# user_interface.net
KiCad netlist of a schematic drawn in Altium Designer
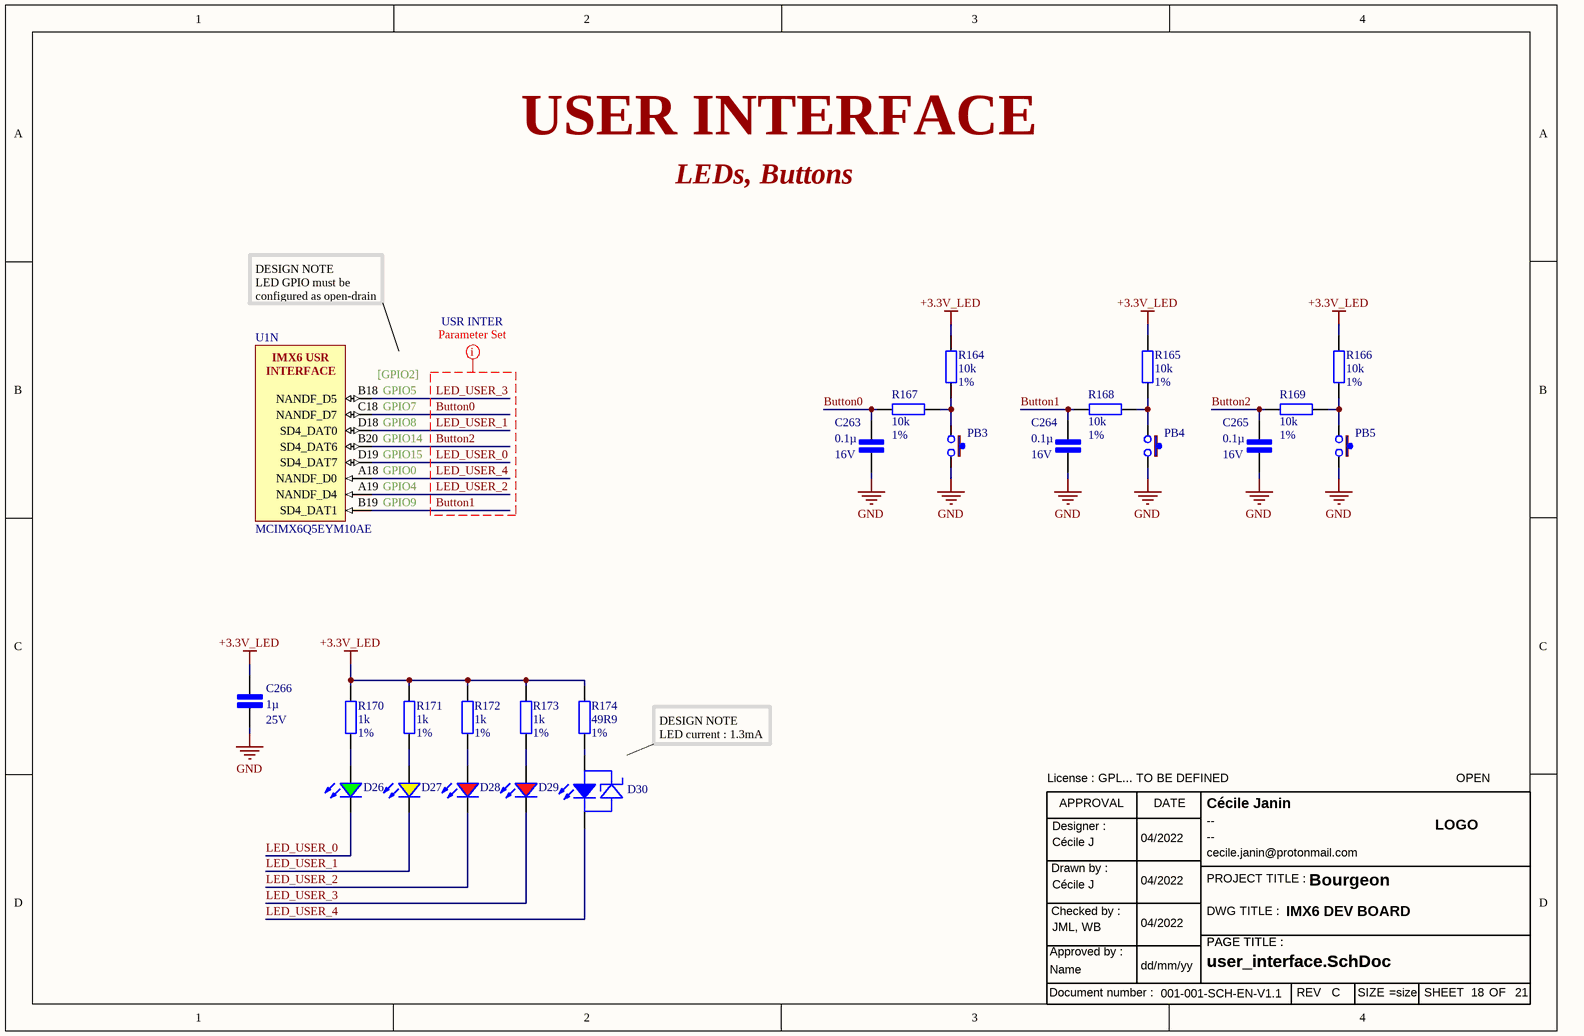
[diagram p0: user_interface.SchDoc]

(export (version "E")
  (design (tool "Eeschema 10.0.6"))
  (components
    (comp (ref "C263")
      (value "0.1µ")
      (footprint "Cap cer 0402/1005")
      (description "cap solid electrolyte 0.1µ 6.3V 10%")
      (fields (field (name "TENSION DU DIÉLECTRIQUE") "16V"))
      (libsource (lib "First Board IMX6") (part "cap 0.1µ 16V"))
    )
    (comp (ref "C264")
      (value "0.1µ")
      (footprint "Cap cer 0402/1005")
      (description "cap solid electrolyte 0.1µ 6.3V 10%")
      (fields (field (name "TENSION DU DIÉLECTRIQUE") "16V"))
      (libsource (lib "First Board IMX6") (part "cap 0.1µ 16V"))
    )
    (comp (ref "C265")
      (value "0.1µ")
      (footprint "Cap cer 0402/1005")
      (description "cap solid electrolyte 0.1µ 6.3V 10%")
      (fields (field (name "TENSION DU DIÉLECTRIQUE") "16V"))
      (libsource (lib "First Board IMX6") (part "cap 0.1µ 16V"))
    )
    (comp (ref "C266")
      (value "1µ")
      (footprint "Cap cer 0402/1005")
      (description "cap cer 1µ 25V 10% X5R 0402")
      (fields (field (name "TENSION DU DIÉLECTRIQUE") "25V"))
      (libsource (lib "First Board IMX6") (part "cap 1µ 25V"))
    )
    (comp (ref "D26")
      (value "Bright Green, 2V, 120deg")
      (footprint "LED green 0603")
      (description "WL-SMCC SMD Mono-color Chip LED Compact, size 0603, Bright Green, 2V, 120deg 150060VS73220")
      (fields (field (name "PART NUMBER") "150060VS73220") (field (name "PUBLISHER") "Wurth Elektronik"))
      (libsource (lib "First Board IMX6") (part "LED green 0603"))
    )
    (comp (ref "D27")
      (value "Yellow, 2V, 120deg")
      (footprint "LED yellow 0603")
      (description "WL-SMCC SMD Mono-color Chip LED Compact, size 0603, Yellow, 2V, 120deg 150060YS73220")
      (fields (field (name "PART NUMBER") "150060YS73220") (field (name "PUBLISHER") "Wurth Elektronik"))
      (libsource (lib "First Board IMX6") (part "LED Yellow 0603"))
    )
    (comp (ref "D28")
      (value "Red, 2V, 120deg")
      (footprint "LED red 0603")
      (description "WL-SMCC SMD Mono-color Chip LED Compact, size 0603, Red, 2V, 120deg 150060RS73220")
      (fields (field (name "PART NUMBER") "150060RS73220") (field (name "PUBLISHER") "Wurth Elektronik"))
      (libsource (lib "First Board IMX6") (part "LED Red 0603"))
    )
    (comp (ref "D29")
      (value "Red, 2V, 120deg")
      (footprint "LED red 0603")
      (description "WL-SMCC SMD Mono-color Chip LED Compact, size 0603, Red, 2V, 120deg 150060RS73220")
      (fields (field (name "PART NUMBER") "150060RS73220") (field (name "PUBLISHER") "Wurth Elektronik"))
      (libsource (lib "First Board IMX6") (part "LED Red 0603"))
    )
    (comp (ref "D30")
      (value "Blue, 3.2V, 120deg")
      (footprint "LED blue 0603")
      (description "WL-SMCC SMD Mono-color Chip LED Compact, size 0603, Blue, 3.2V, 120deg 150060BS73220")
      (fields (field (name "PART NUMBER") "150060BS73220") (field (name "PUBLISHER") "Wurth Elektronik"))
      (libsource (lib "First Board IMX6") (part "LED blue 0603"))
    )
    (comp (ref "PB3")
      (value "pb_434121025816")
      (footprint "pb_434121025816")
      (libsource (lib "First Board IMX6") (part "pb_434121025816"))
    )
    (comp (ref "PB4")
      (value "pb_434121025816")
      (footprint "pb_434121025816")
      (libsource (lib "First Board IMX6") (part "pb_434121025816"))
    )
    (comp (ref "PB5")
      (value "pb_434121025816")
      (footprint "pb_434121025816")
      (libsource (lib "First Board IMX6") (part "pb_434121025816"))
    )
    (comp (ref "R164")
      (value "10k")
      (footprint "Res 0402/1005")
      (description "res 10k 1% 0402")
      (fields (field (name "POURCENTAGE") "1%"))
      (libsource (lib "First Board IMX6") (part "res 10k 1%"))
    )
    (comp (ref "R165")
      (value "10k")
      (footprint "Res 0402/1005")
      (description "res 10k 1% 0402")
      (fields (field (name "POURCENTAGE") "1%"))
      (libsource (lib "First Board IMX6") (part "res 10k 1%"))
    )
    (comp (ref "R166")
      (value "10k")
      (footprint "Res 0402/1005")
      (description "res 10k 1% 0402")
      (fields (field (name "POURCENTAGE") "1%"))
      (libsource (lib "First Board IMX6") (part "res 10k 1%"))
    )
    (comp (ref "R167")
      (value "10k")
      (footprint "Res 0402/1005")
      (description "res 10k 1% 0402")
      (fields (field (name "POURCENTAGE") "1%"))
      (libsource (lib "First Board IMX6") (part "res 10k 1%"))
    )
    (comp (ref "R168")
      (value "10k")
      (footprint "Res 0402/1005")
      (description "res 10k 1% 0402")
      (fields (field (name "POURCENTAGE") "1%"))
      (libsource (lib "First Board IMX6") (part "res 10k 1%"))
    )
    (comp (ref "R169")
      (value "10k")
      (footprint "Res 0402/1005")
      (description "res 10k 1% 0402")
      (fields (field (name "POURCENTAGE") "1%"))
      (libsource (lib "First Board IMX6") (part "res 10k 1%"))
    )
    (comp (ref "R170")
      (value "1k")
      (footprint "Res 0402/1005")
      (description "res 1k 1% 0402")
      (fields (field (name "POURCENTAGE") "1%"))
      (libsource (lib "First Board IMX6") (part "res 1k 1%"))
    )
    (comp (ref "R171")
      (value "1k")
      (footprint "Res 0402/1005")
      (description "res 1k 1% 0402")
      (fields (field (name "POURCENTAGE") "1%"))
      (libsource (lib "First Board IMX6") (part "res 1k 1%"))
    )
    (comp (ref "R172")
      (value "1k")
      (footprint "Res 0402/1005")
      (description "res 1k 1% 0402")
      (fields (field (name "POURCENTAGE") "1%"))
      (libsource (lib "First Board IMX6") (part "res 1k 1%"))
    )
    (comp (ref "R173")
      (value "1k")
      (footprint "Res 0402/1005")
      (description "res 1k 1% 0402")
      (fields (field (name "POURCENTAGE") "1%"))
      (libsource (lib "First Board IMX6") (part "res 1k 1%"))
    )
    (comp (ref "R174")
      (value "49R9")
      (footprint "Res 0402/1005")
      (description "res 49R9 ohm 1% 0402")
      (fields (field (name "POURCENTAGE") "1%"))
      (libsource (lib "First Board IMX6") (part "res 49R9 1%"))
    )
    (comp (ref "TB17")
      (value "Title bloc ANSI modified")
      (libsource (lib "First Board IMX6") (part "Title bloc ANSI"))
    )
    (comp (ref "U1")
      (value "MCIMX6Q5EYM10AE")
      (footprint "FRES-2197-01")
      (fields
        (field (name "PARTNUMBER") "MCIMX6Q5EYM10ACR")
        (field (name "MANUFACTURER") "Freescale Semiconductor")
      )
      (libsource (lib "First Board IMX6") (part "IMX6Q5EYM10AE"))
    )
  )
  (nets
    (net (code "1") (name "+3.3V_LED") (class "Default")
      (node (ref "C266") (pin "1") (pinfunction "3_1") (pintype "passive"))
      (node (ref "R164") (pin "2") (pintype "passive"))
      (node (ref "R165") (pin "2") (pintype "passive"))
      (node (ref "R166") (pin "2") (pintype "passive"))
      (node (ref "R170") (pin "2") (pintype "passive"))
      (node (ref "R171") (pin "2") (pintype "passive"))
      (node (ref "R172") (pin "2") (pintype "passive"))
      (node (ref "R173") (pin "2") (pintype "passive"))
      (node (ref "R174") (pin "2") (pintype "passive"))
    )
    (net (code "2") (name "/Button0") (class "Default")
      (node (ref "C263") (pin "1") (pinfunction "3_1") (pintype "passive"))
      (node (ref "R167") (pin "2") (pintype "passive"))
      (node (ref "U1") (pin "C18") (pinfunction "NANDF_D7_C18") (pintype "bidirectional"))
    )
    (net (code "3") (name "/Button1") (class "Default")
      (node (ref "C264") (pin "1") (pinfunction "3_1") (pintype "passive"))
      (node (ref "R168") (pin "2") (pintype "passive"))
      (node (ref "U1") (pin "B19") (pinfunction "SD4_DAT1_B19") (pintype "input"))
    )
    (net (code "4") (name "/Button2") (class "Default")
      (node (ref "C265") (pin "1") (pinfunction "3_1") (pintype "passive"))
      (node (ref "R169") (pin "2") (pintype "passive"))
      (node (ref "U1") (pin "B20") (pinfunction "SD4_DAT6_B20") (pintype "bidirectional"))
    )
    (net (code "5") (name "/LED_USER_0") (class "Default")
      (node (ref "D26") (pin "1") (pinfunction "K_1") (pintype "passive"))
      (node (ref "U1") (pin "D19") (pinfunction "SD4_DAT7_D19") (pintype "bidirectional"))
    )
    (net (code "6") (name "/LED_USER_1") (class "Default")
      (node (ref "D27") (pin "1") (pinfunction "K_1") (pintype "passive"))
      (node (ref "U1") (pin "D18") (pinfunction "SD4_DAT0_D18") (pintype "bidirectional"))
    )
    (net (code "7") (name "/LED_USER_2") (class "Default")
      (node (ref "D28") (pin "1") (pinfunction "K_1") (pintype "passive"))
      (node (ref "U1") (pin "A19") (pinfunction "NANDF_D4_A19") (pintype "input"))
    )
    (net (code "8") (name "/LED_USER_3") (class "Default")
      (node (ref "D29") (pin "1") (pinfunction "K_1") (pintype "passive"))
      (node (ref "U1") (pin "B18") (pinfunction "NANDF_D5_B18") (pintype "bidirectional"))
    )
    (net (code "9") (name "/LED_USER_4") (class "Default")
      (node (ref "D30") (pin "1") (pinfunction "K_1") (pintype "passive"))
      (node (ref "U1") (pin "A18") (pinfunction "NANDF_D0_A18") (pintype "input"))
    )
    (net (code "10") (name "GND") (class "Default")
      (node (ref "C263") (pin "2") (pinfunction "4_2") (pintype "passive"))
      (node (ref "C264") (pin "2") (pinfunction "4_2") (pintype "passive"))
      (node (ref "C265") (pin "2") (pinfunction "4_2") (pintype "passive"))
      (node (ref "C266") (pin "2") (pinfunction "4_2") (pintype "passive"))
      (node (ref "PB3") (pin "2") (pinfunction "2_2") (pintype "passive"))
      (node (ref "PB4") (pin "2") (pinfunction "2_2") (pintype "passive"))
      (node (ref "PB5") (pin "2") (pinfunction "2_2") (pintype "passive"))
    )
    (net (code "11") (name "Net-(D26-A)") (class "Default")
      (node (ref "D26") (pin "2") (pinfunction "A_2") (pintype "passive"))
      (node (ref "R170") (pin "1") (pintype "passive"))
    )
    (net (code "12") (name "Net-(D27-A)") (class "Default")
      (node (ref "D27") (pin "2") (pinfunction "A_2") (pintype "passive"))
      (node (ref "R171") (pin "1") (pintype "passive"))
    )
    (net (code "13") (name "Net-(D28-A)") (class "Default")
      (node (ref "D28") (pin "2") (pinfunction "A_2") (pintype "passive"))
      (node (ref "R172") (pin "1") (pintype "passive"))
    )
    (net (code "14") (name "Net-(D29-A)") (class "Default")
      (node (ref "D29") (pin "2") (pinfunction "A_2") (pintype "passive"))
      (node (ref "R173") (pin "1") (pintype "passive"))
    )
    (net (code "15") (name "Net-(D30-A)") (class "Default")
      (node (ref "D30") (pin "2") (pinfunction "A_2") (pintype "passive"))
      (node (ref "R174") (pin "1") (pintype "passive"))
    )
    (net (code "16") (name "Net-(PB3-Pad1)") (class "Default")
      (node (ref "PB3") (pin "1") (pinfunction "1_1") (pintype "passive"))
      (node (ref "R164") (pin "1") (pintype "passive"))
      (node (ref "R167") (pin "1") (pintype "passive"))
    )
    (net (code "17") (name "Net-(PB4-Pad1)") (class "Default")
      (node (ref "PB4") (pin "1") (pinfunction "1_1") (pintype "passive"))
      (node (ref "R165") (pin "1") (pintype "passive"))
      (node (ref "R168") (pin "1") (pintype "passive"))
    )
    (net (code "18") (name "Net-(PB5-Pad1)") (class "Default")
      (node (ref "PB5") (pin "1") (pinfunction "1_1") (pintype "passive"))
      (node (ref "R166") (pin "1") (pintype "passive"))
      (node (ref "R169") (pin "1") (pintype "passive"))
    )
  )
)
